# beijing_rev_A.net
KiCad netlist of a schematic drawn in EAGLE
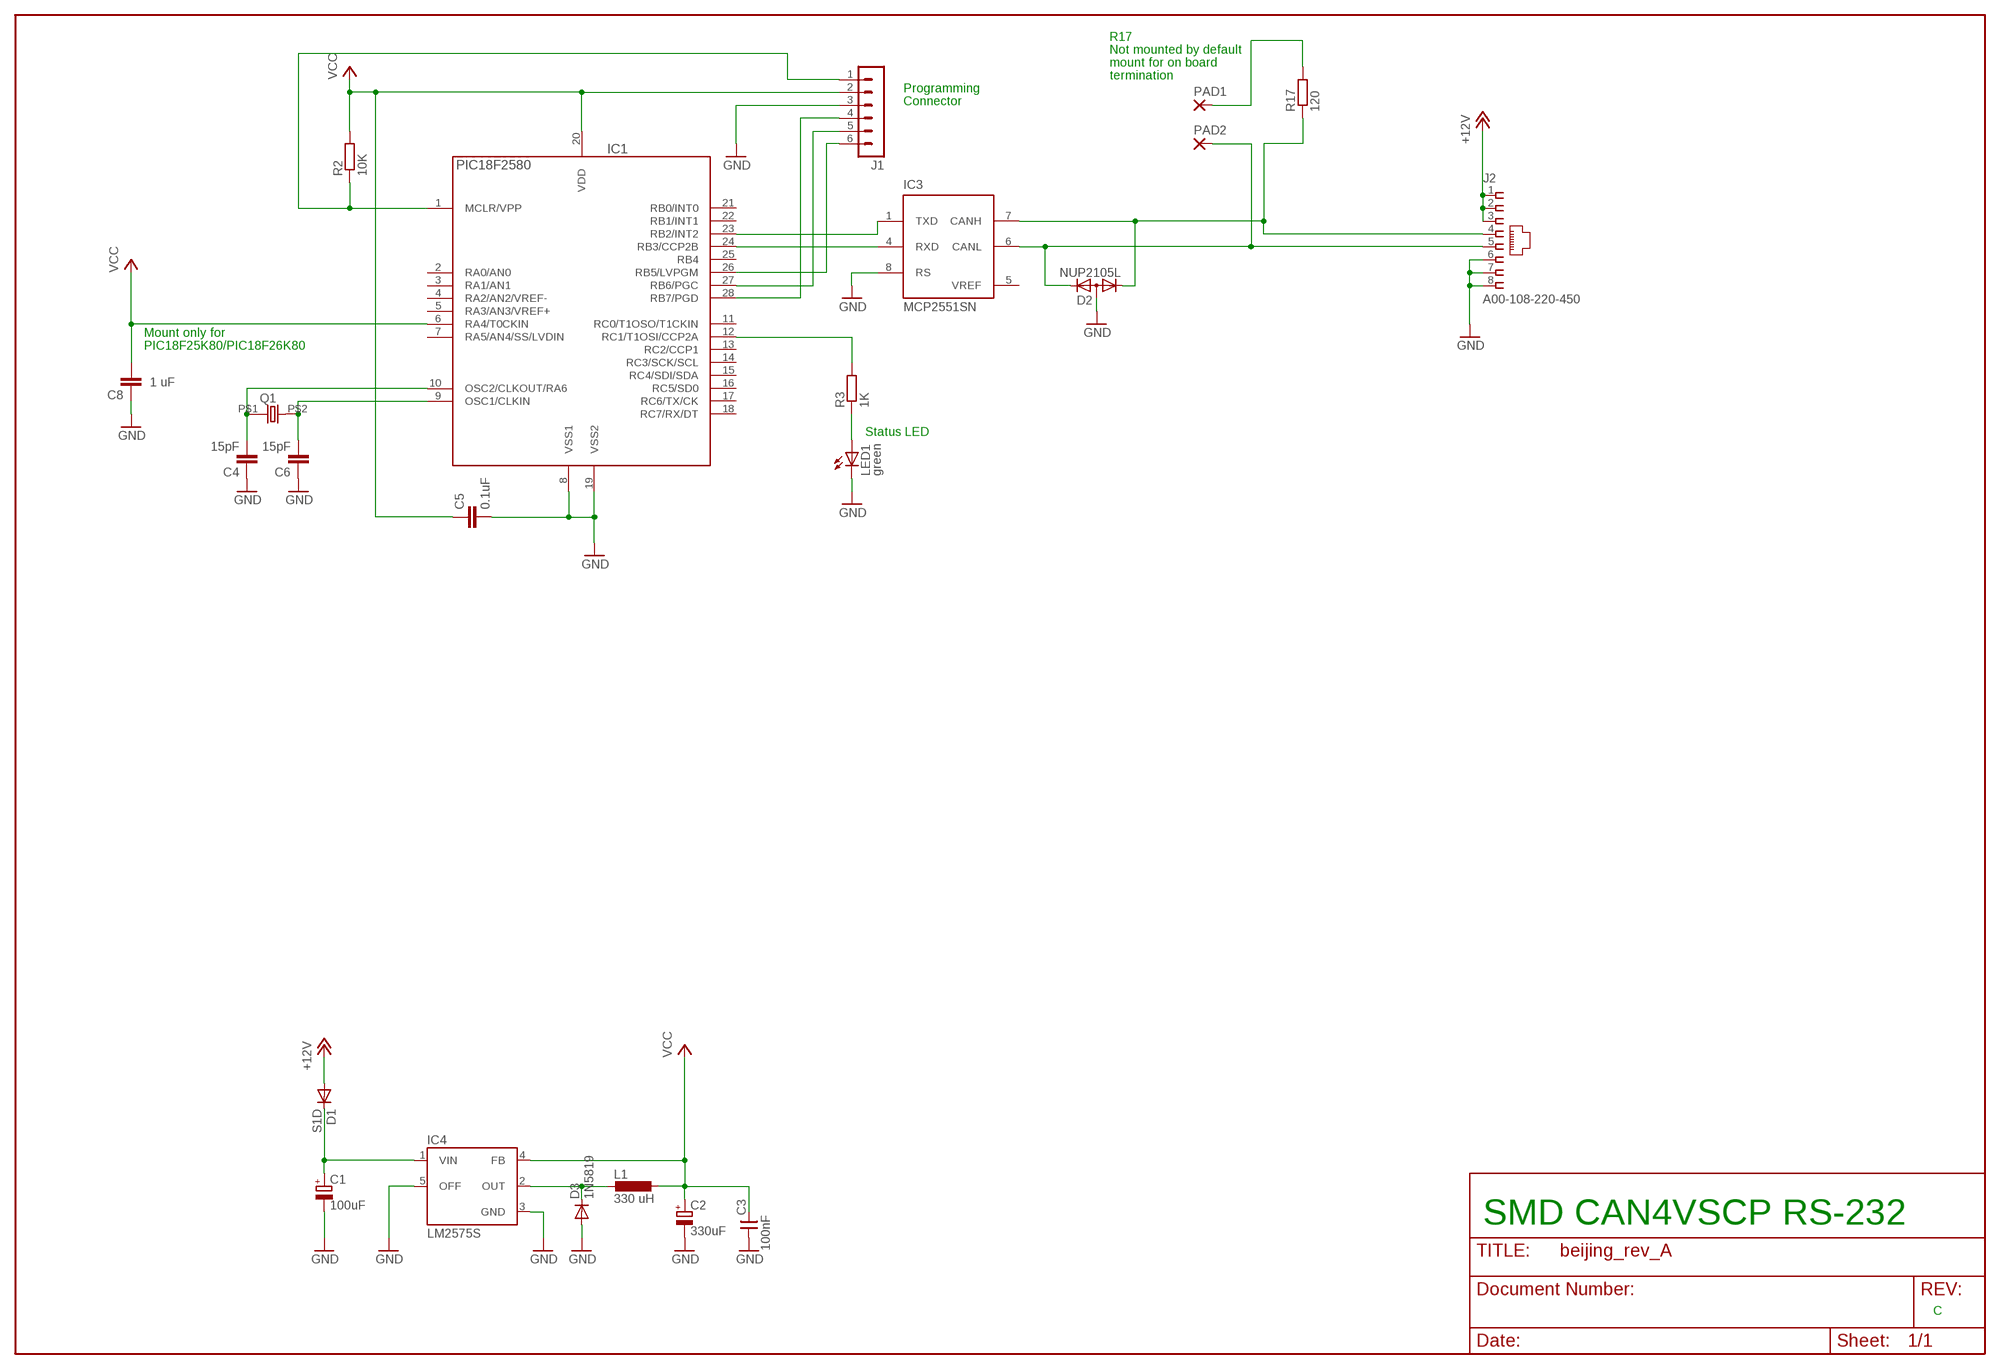
[diagram p0: schematic, sheet 1]

(export (version "E")
  (design (tool "Eeschema 10.0.6"))
  (components
    (comp (ref "C1")
      (value "100uF")
      (footprint "eagle-import:PANASONIC_D")
      (libsource (lib "eagle-import") (part "CPOL-EUD"))
    )
    (comp (ref "C2")
      (value "330uF")
      (footprint "eagle-import:PANASONIC_D")
      (libsource (lib "eagle-import") (part "CPOL-EUD"))
    )
    (comp (ref "C3")
      (value "100nF")
      (footprint "eagle-import:0805")
      (libsource (lib "eagle-import") (part "CNP-0805"))
    )
    (comp (ref "C4")
      (value "15pF")
      (footprint "eagle-import:C0805")
      (libsource (lib "eagle-import") (part "C-EUC0805"))
    )
    (comp (ref "C5")
      (value "0.1uF")
      (footprint "eagle-import:C0805")
      (libsource (lib "eagle-import") (part "C-EUC0805"))
    )
    (comp (ref "C6")
      (value "15pF")
      (footprint "eagle-import:C0805")
      (libsource (lib "eagle-import") (part "C-EUC0805"))
    )
    (comp (ref "C8")
      (value "1 uF")
      (footprint "eagle-import:C0805")
      (libsource (lib "eagle-import") (part "C-EUC0805"))
    )
    (comp (ref "D1")
      (value "S1D")
      (footprint "eagle-import:SOD123")
      (libsource (lib "eagle-import") (part "DIODE-SOD123"))
    )
    (comp (ref "D2")
      (value "NUP2105L")
      (footprint "eagle-import:SOT23")
      (libsource (lib "eagle-import") (part "DIODE-2CA|ACSOT23"))
    )
    (comp (ref "D3")
      (value "1N5819")
      (footprint "eagle-import:SOD123")
      (libsource (lib "eagle-import") (part "DIODE-SOD123"))
    )
    (comp (ref "IC1")
      (value "PIC18F2580")
      (footprint "eagle-import:SO28")
      (libsource (lib "eagle-import") (part "PIC18F252-?I/SOL"))
    )
    (comp (ref "IC3")
      (value "MCP2551SN")
      (footprint "eagle-import:SO-08")
      (libsource (lib "eagle-import") (part "MCP2551SN"))
    )
    (comp (ref "IC4")
      (value "LM2575S")
      (footprint "eagle-import:TO263-5")
      (libsource (lib "eagle-import") (part "LM2575S"))
    )
    (comp (ref "J1")
      (value "MA06-1")
      (footprint "eagle-import:MA06-1")
      (libsource (lib "eagle-import") (part "MA06-1"))
    )
    (comp (ref "J2")
      (value "A00-108-220-450")
      (footprint "eagle-import:RJ-45")
      (libsource (lib "eagle-import") (part "A00-108-220-450"))
    )
    (comp (ref "L1")
      (value "330 uH")
      (footprint "eagle-import:DO3316P")
      (libsource (lib "eagle-import") (part "DO3316P"))
    )
    (comp (ref "LED1")
      (value "green")
      (footprint "eagle-import:CHIPLED_0805")
      (libsource (lib "eagle-import") (part "LEDCHIPLED_0805"))
    )
    (comp (ref "PAD1")
      (value "1,6/0,8")
      (footprint "eagle-import:1,6_0,8")
      (libsource (lib "eagle-import") (part "1,6/0,8"))
    )
    (comp (ref "PAD2")
      (value "1,6/0,8")
      (footprint "eagle-import:1,6_0,8")
      (libsource (lib "eagle-import") (part "1,6/0,8"))
    )
    (comp (ref "Q1")
      (value "HC-49S")
      (footprint "eagle-import:9C")
      (libsource (lib "eagle-import") (part "HC-49S"))
    )
    (comp (ref "R2")
      (value "10K")
      (footprint "eagle-import:R0805")
      (libsource (lib "eagle-import") (part "R-EU_R0805"))
    )
    (comp (ref "R3")
      (value "1K")
      (footprint "eagle-import:R0805")
      (libsource (lib "eagle-import") (part "R-EU_R0805"))
    )
    (comp (ref "R17")
      (value "120")
      (footprint "eagle-import:R0805")
      (libsource (lib "eagle-import") (part "R-EU_R0805"))
    )
  )
  (nets
    (net (code "1") (name "+12V") (class "Default")
      (node (ref "D1") (pin "A") (pinfunction "A_A") (pintype "passive"))
      (node (ref "J2") (pin "1") (pinfunction "1_1") (pintype "passive"))
      (node (ref "J2") (pin "2") (pinfunction "2_2") (pintype "passive"))
      (node (ref "J2") (pin "3") (pinfunction "3_3") (pintype "passive"))
    )
    (net (code "2") (name "/VREF") (class "Default")
      (node (ref "IC3") (pin "5") (pinfunction "VREF_5") (pintype "power_in"))
    )
    (net (code "3") (name "GND") (class "Default")
      (node (ref "C1") (pin "-") (pinfunction "-_-") (pintype "passive"))
      (node (ref "C2") (pin "-") (pinfunction "-_-") (pintype "passive"))
      (node (ref "C3") (pin "1") (pinfunction "1_1") (pintype "passive"))
      (node (ref "C4") (pin "1") (pinfunction "1_1") (pintype "passive"))
      (node (ref "C5") (pin "2") (pinfunction "2_2") (pintype "passive"))
      (node (ref "C6") (pin "1") (pinfunction "1_1") (pintype "passive"))
      (node (ref "C8") (pin "1") (pinfunction "1_1") (pintype "passive"))
      (node (ref "D2") (pin "3") (pinfunction "A_3") (pintype "passive"))
      (node (ref "D3") (pin "A") (pinfunction "A_A") (pintype "passive"))
      (node (ref "IC1") (pin "19") (pinfunction "VSS2_19") (pintype "power_in"))
      (node (ref "IC1") (pin "8") (pinfunction "VSS1_8") (pintype "power_in"))
      (node (ref "IC3") (pin "8") (pinfunction "RS_8") (pintype "input"))
      (node (ref "IC4") (pin "3") (pinfunction "GND_3") (pintype "power_in"))
      (node (ref "IC4") (pin "5") (pinfunction "OFF_5") (pintype "input"))
      (node (ref "J1") (pin "3") (pinfunction "3_3") (pintype "passive"))
      (node (ref "J2") (pin "6") (pinfunction "6_6") (pintype "passive"))
      (node (ref "J2") (pin "7") (pinfunction "7_7") (pintype "passive"))
      (node (ref "J2") (pin "8") (pinfunction "8_8") (pintype "passive"))
      (node (ref "LED1") (pin "C") (pinfunction "C_C") (pintype "passive"))
    )
    (net (code "4") (name "Net-(D2-K1)") (class "Default")
      (node (ref "D2") (pin "1") (pinfunction "K1_1") (pintype "passive"))
      (node (ref "IC3") (pin "7") (pinfunction "CANH_7") (pintype "bidirectional"))
      (node (ref "J2") (pin "4") (pinfunction "4_4") (pintype "passive"))
      (node (ref "R17") (pin "1") (pinfunction "1_1") (pintype "passive"))
    )
    (net (code "5") (name "Net-(D2-K2)") (class "Default")
      (node (ref "D2") (pin "2") (pinfunction "K2_2") (pintype "passive"))
      (node (ref "IC3") (pin "6") (pinfunction "CANL_6") (pintype "bidirectional"))
      (node (ref "J2") (pin "5") (pinfunction "5_5") (pintype "passive"))
      (node (ref "PAD2") (pin "1") (pinfunction "P_1") (pintype "passive"))
    )
    (net (code "6") (name "Net-(IC1-MCLR{slash}VPP)") (class "Default")
      (node (ref "IC1") (pin "1") (pinfunction "MCLR/VPP_1") (pintype "input"))
      (node (ref "J1") (pin "1") (pinfunction "1_1") (pintype "passive"))
      (node (ref "R2") (pin "1") (pinfunction "1_1") (pintype "passive"))
    )
    (net (code "7") (name "Net-(IC1-OSC1{slash}CLKIN)") (class "Default")
      (node (ref "C6") (pin "2") (pinfunction "2_2") (pintype "passive"))
      (node (ref "IC1") (pin "9") (pinfunction "OSC1/CLKIN_9") (pintype "input"))
      (node (ref "Q1") (pin "P$2") (pinfunction "2_P$2") (pintype "passive"))
    )
    (net (code "8") (name "Net-(IC1-OSC2{slash}CLKOUT{slash}RA6)") (class "Default")
      (node (ref "C4") (pin "2") (pinfunction "2_2") (pintype "passive"))
      (node (ref "IC1") (pin "10") (pinfunction "OSC2/CLKOUT/RA6_10") (pintype "output"))
      (node (ref "Q1") (pin "P$1") (pinfunction "1_P$1") (pintype "passive"))
    )
    (net (code "9") (name "Net-(IC1-RB2{slash}INT2)") (class "Default")
      (node (ref "IC1") (pin "23") (pinfunction "RB2/INT2_23") (pintype "bidirectional"))
      (node (ref "IC3") (pin "1") (pinfunction "TXD_1") (pintype "input"))
    )
    (net (code "10") (name "Net-(IC1-RB3{slash}CCP2B)") (class "Default")
      (node (ref "IC1") (pin "24") (pinfunction "RB3/CCP2B_24") (pintype "bidirectional"))
      (node (ref "IC3") (pin "4") (pinfunction "RXD_4") (pintype "output"))
    )
    (net (code "11") (name "Net-(IC1-RB5{slash}LVPGM)") (class "Default")
      (node (ref "IC1") (pin "26") (pinfunction "RB5/LVPGM_26") (pintype "bidirectional"))
      (node (ref "J1") (pin "6") (pinfunction "6_6") (pintype "passive"))
    )
    (net (code "12") (name "Net-(IC1-RB6{slash}PGC)") (class "Default")
      (node (ref "IC1") (pin "27") (pinfunction "RB6/PGC_27") (pintype "bidirectional"))
      (node (ref "J1") (pin "5") (pinfunction "5_5") (pintype "passive"))
    )
    (net (code "13") (name "Net-(IC1-RB7{slash}PGD)") (class "Default")
      (node (ref "IC1") (pin "28") (pinfunction "RB7/PGD_28") (pintype "bidirectional"))
      (node (ref "J1") (pin "4") (pinfunction "4_4") (pintype "passive"))
    )
    (net (code "14") (name "Net-(IC1-RC1{slash}T1OSI{slash}CCP2A)") (class "Default")
      (node (ref "IC1") (pin "12") (pinfunction "RC1/T1OSI/CCP2A_12") (pintype "bidirectional"))
      (node (ref "R3") (pin "2") (pinfunction "2_2") (pintype "passive"))
    )
    (net (code "15") (name "Net-(IC4-OUT)") (class "Default")
      (node (ref "D3") (pin "C") (pinfunction "C_C") (pintype "passive"))
      (node (ref "IC4") (pin "2") (pinfunction "OUT_2") (pintype "output"))
      (node (ref "L1") (pin "1") (pinfunction "1_1") (pintype "passive"))
    )
    (net (code "16") (name "Net-(IC4-VIN)") (class "Default")
      (node (ref "C1") (pin "+") (pinfunction "+_+") (pintype "passive"))
      (node (ref "D1") (pin "C") (pinfunction "C_C") (pintype "passive"))
      (node (ref "IC4") (pin "1") (pinfunction "VIN_1") (pintype "power_in"))
    )
    (net (code "17") (name "Net-(LED1-PadA)") (class "Default")
      (node (ref "LED1") (pin "A") (pinfunction "A_A") (pintype "passive"))
      (node (ref "R3") (pin "1") (pinfunction "1_1") (pintype "passive"))
    )
    (net (code "18") (name "Net-(PAD1-P)") (class "Default")
      (node (ref "PAD1") (pin "1") (pinfunction "P_1") (pintype "passive"))
      (node (ref "R17") (pin "2") (pinfunction "2_2") (pintype "passive"))
    )
    (net (code "19") (name "VCC") (class "Default")
      (node (ref "C2") (pin "+") (pinfunction "+_+") (pintype "passive"))
      (node (ref "C3") (pin "2") (pinfunction "2_2") (pintype "passive"))
      (node (ref "C5") (pin "1") (pinfunction "1_1") (pintype "passive"))
      (node (ref "C8") (pin "2") (pinfunction "2_2") (pintype "passive"))
      (node (ref "IC1") (pin "20") (pinfunction "VDD_20") (pintype "power_in"))
      (node (ref "IC1") (pin "6") (pinfunction "RA4/T0CKIN_6") (pintype "open_collector"))
      (node (ref "IC4") (pin "4") (pinfunction "FB_4") (pintype "input"))
      (node (ref "J1") (pin "2") (pinfunction "2_2") (pintype "passive"))
      (node (ref "L1") (pin "2") (pinfunction "2_2") (pintype "passive"))
      (node (ref "R2") (pin "2") (pinfunction "2_2") (pintype "passive"))
    )
    (net (code "20") (name "unconnected-(IC1-RA0{slash}AN0-Pad2)") (class "Default")
      (node (ref "IC1") (pin "2") (pinfunction "RA0/AN0_2") (pintype "bidirectional"))
    )
    (net (code "21") (name "unconnected-(IC1-RA1{slash}AN1-Pad3)") (class "Default")
      (node (ref "IC1") (pin "3") (pinfunction "RA1/AN1_3") (pintype "bidirectional"))
    )
    (net (code "22") (name "unconnected-(IC1-RA2{slash}AN2{slash}VREF--Pad4)") (class "Default")
      (node (ref "IC1") (pin "4") (pinfunction "RA2/AN2/VREF-_4") (pintype "bidirectional"))
    )
    (net (code "23") (name "unconnected-(IC1-RA3{slash}AN3{slash}VREF+-Pad5)") (class "Default")
      (node (ref "IC1") (pin "5") (pinfunction "RA3/AN3/VREF+_5") (pintype "bidirectional"))
    )
    (net (code "24") (name "unconnected-(IC1-RA5{slash}AN4{slash}SS{slash}LVDIN-Pad7)") (class "Default")
      (node (ref "IC1") (pin "7") (pinfunction "RA5/AN4/SS/LVDIN_7") (pintype "bidirectional"))
    )
    (net (code "25") (name "unconnected-(IC1-RB0{slash}INT0-Pad21)") (class "Default")
      (node (ref "IC1") (pin "21") (pinfunction "RB0/INT0_21") (pintype "bidirectional"))
    )
    (net (code "26") (name "unconnected-(IC1-RB1{slash}INT1-Pad22)") (class "Default")
      (node (ref "IC1") (pin "22") (pinfunction "RB1/INT1_22") (pintype "bidirectional"))
    )
    (net (code "27") (name "unconnected-(IC1-RB4-Pad25)") (class "Default")
      (node (ref "IC1") (pin "25") (pinfunction "RB4_25") (pintype "bidirectional"))
    )
    (net (code "28") (name "unconnected-(IC1-RC0{slash}T1OSO{slash}T1CKIN-Pad11)") (class "Default")
      (node (ref "IC1") (pin "11") (pinfunction "RC0/T1OSO/T1CKIN_11") (pintype "bidirectional"))
    )
    (net (code "29") (name "unconnected-(IC1-RC2{slash}CCP1-Pad13)") (class "Default")
      (node (ref "IC1") (pin "13") (pinfunction "RC2/CCP1_13") (pintype "bidirectional"))
    )
    (net (code "30") (name "unconnected-(IC1-RC3{slash}SCK{slash}SCL-Pad14)") (class "Default")
      (node (ref "IC1") (pin "14") (pinfunction "RC3/SCK/SCL_14") (pintype "bidirectional"))
    )
    (net (code "31") (name "unconnected-(IC1-RC4{slash}SDI{slash}SDA-Pad15)") (class "Default")
      (node (ref "IC1") (pin "15") (pinfunction "RC4/SDI/SDA_15") (pintype "bidirectional"))
    )
    (net (code "32") (name "unconnected-(IC1-RC5{slash}SD0-Pad16)") (class "Default")
      (node (ref "IC1") (pin "16") (pinfunction "RC5/SD0_16") (pintype "bidirectional"))
    )
    (net (code "33") (name "unconnected-(IC1-RC6{slash}TX{slash}CK-Pad17)") (class "Default")
      (node (ref "IC1") (pin "17") (pinfunction "RC6/TX/CK_17") (pintype "bidirectional"))
    )
    (net (code "34") (name "unconnected-(IC1-RC7{slash}RX{slash}DT-Pad18)") (class "Default")
      (node (ref "IC1") (pin "18") (pinfunction "RC7/RX/DT_18") (pintype "bidirectional"))
    )
  )
)
